# Output_Expander_IC.net
KiCad netlist of a schematic drawn in Altium Designer
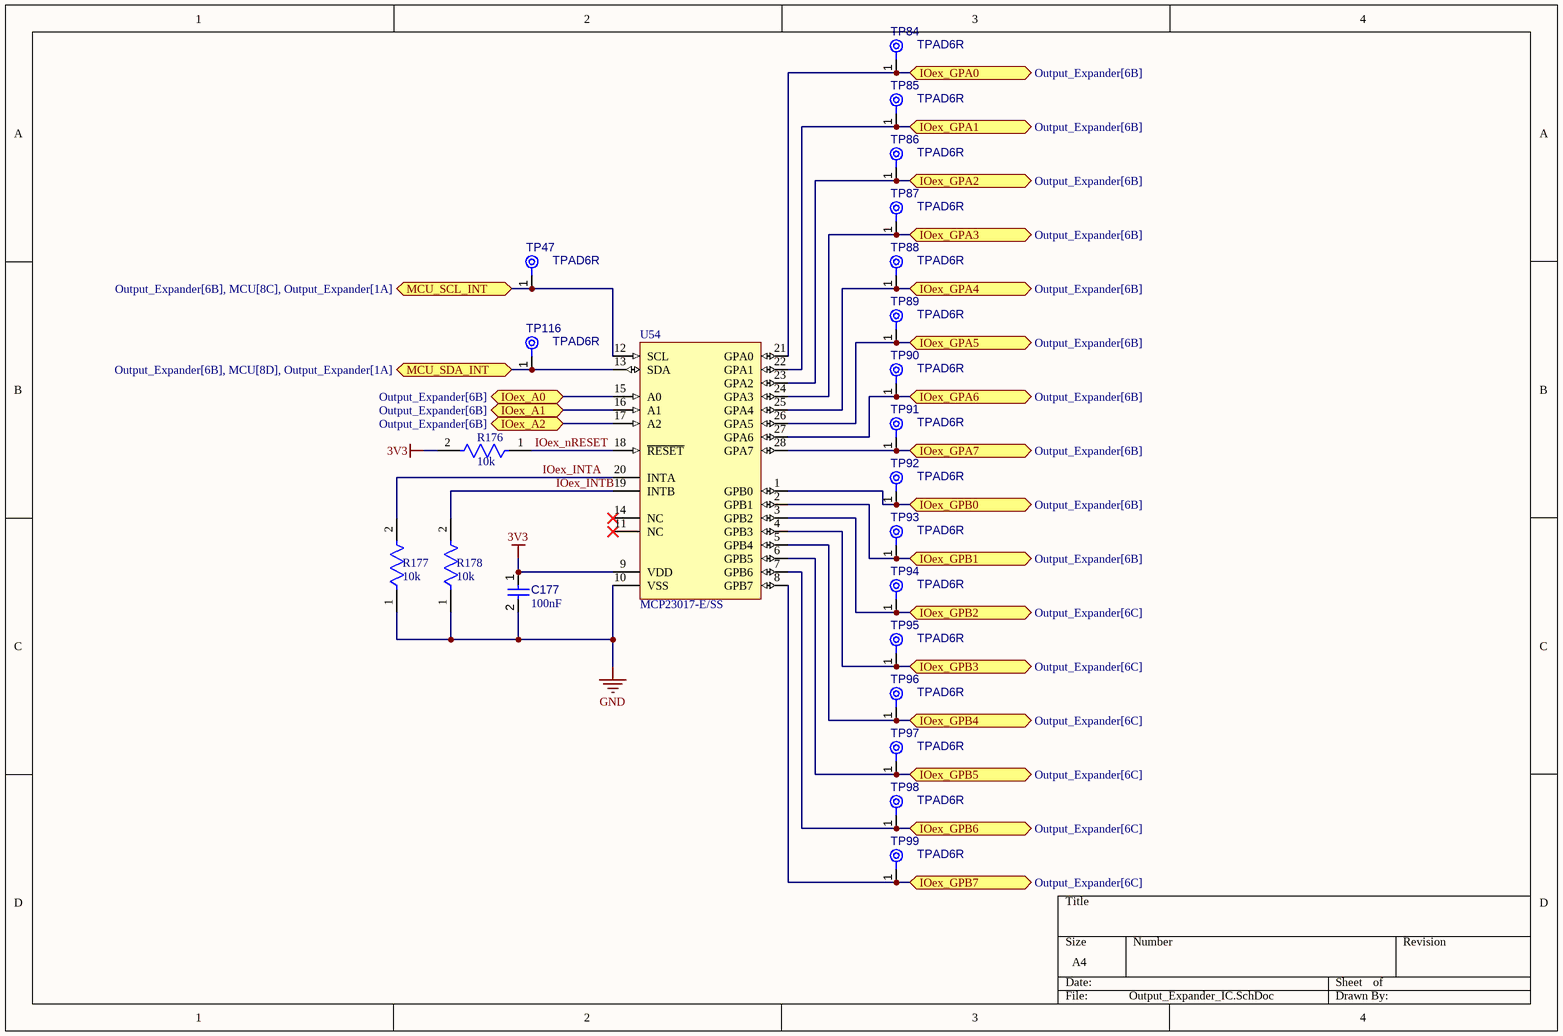
[diagram p0:  Output_Expander_IC.SchDoc]

(export (version "E")
  (design (tool "Eeschema 10.0.6"))
  (components
    (comp (ref "C177")
      (value "100nF")
      (footprint "CAPC1608X90X40NL10T20")
      (description "Chip Capacitor, 100 nF, +/- 10%, 50 V, 0603 (1608 Metric)")
      (fields (field (name "TOLERANCE") "10%") (field (name "Comment") "Capacitor 100 nF +/-10% 50 V 0603"))
      (libsource (lib "HIL RIG FYP") (part "CAP-NP-2"))
    )
    (comp (ref "R176")
      (value "10k")
      (footprint "FP-RT0603-IPC_C")
      (description "Res Thin Film 0603 10K Ohm 0.1% 1/10W ¦25ppm/¦C SMD Paper T/R")
      (fields (field (name "TOLERANCE") "0.1%") (field (name "Comment") "RT0603BRD0710KL"))
      (libsource (lib "HIL RIG FYP") (part "1029c3af85768c4190bb7ad29bc67b5"))
    )
    (comp (ref "R177")
      (value "10k")
      (footprint "FP-RT0603-IPC_C")
      (description "Res Thin Film 0603 10K Ohm 0.1% 1/10W ¦25ppm/¦C SMD Paper T/R")
      (fields (field (name "TOLERANCE") "0.1%") (field (name "Comment") "RT0603BRD0710KL"))
      (libsource (lib "HIL RIG FYP") (part "1029c3af85768c4190bb7ad29bc67b5"))
    )
    (comp (ref "R178")
      (value "10k")
      (footprint "FP-RT0603-IPC_C")
      (description "Res Thin Film 0603 10K Ohm 0.1% 1/10W ¦25ppm/¦C SMD Paper T/R")
      (fields (field (name "TOLERANCE") "0.1%") (field (name "Comment") "RT0603BRD0710KL"))
      (libsource (lib "HIL RIG FYP") (part "1029c3af85768c4190bb7ad29bc67b5"))
    )
    (comp (ref "TP47")
      (value "TPAD6R")
      (footprint "TP06R")
      (description "0.6mm round")
      (libsource (lib "HIL RIG FYP") (part "CMP-001-0001-4"))
    )
    (comp (ref "TP84")
      (value "TPAD6R")
      (footprint "TP06R")
      (description "0.6mm round")
      (libsource (lib "HIL RIG FYP") (part "CMP-001-0001-4"))
    )
    (comp (ref "TP85")
      (value "TPAD6R")
      (footprint "TP06R")
      (description "0.6mm round")
      (libsource (lib "HIL RIG FYP") (part "CMP-001-0001-4"))
    )
    (comp (ref "TP86")
      (value "TPAD6R")
      (footprint "TP06R")
      (description "0.6mm round")
      (libsource (lib "HIL RIG FYP") (part "CMP-001-0001-4"))
    )
    (comp (ref "TP87")
      (value "TPAD6R")
      (footprint "TP06R")
      (description "0.6mm round")
      (libsource (lib "HIL RIG FYP") (part "CMP-001-0001-4"))
    )
    (comp (ref "TP88")
      (value "TPAD6R")
      (footprint "TP06R")
      (description "0.6mm round")
      (libsource (lib "HIL RIG FYP") (part "CMP-001-0001-4"))
    )
    (comp (ref "TP89")
      (value "TPAD6R")
      (footprint "TP06R")
      (description "0.6mm round")
      (libsource (lib "HIL RIG FYP") (part "CMP-001-0001-4"))
    )
    (comp (ref "TP90")
      (value "TPAD6R")
      (footprint "TP06R")
      (description "0.6mm round")
      (libsource (lib "HIL RIG FYP") (part "CMP-001-0001-4"))
    )
    (comp (ref "TP91")
      (value "TPAD6R")
      (footprint "TP06R")
      (description "0.6mm round")
      (libsource (lib "HIL RIG FYP") (part "CMP-001-0001-4"))
    )
    (comp (ref "TP92")
      (value "TPAD6R")
      (footprint "TP06R")
      (description "0.6mm round")
      (libsource (lib "HIL RIG FYP") (part "CMP-001-0001-4"))
    )
    (comp (ref "TP93")
      (value "TPAD6R")
      (footprint "TP06R")
      (description "0.6mm round")
      (libsource (lib "HIL RIG FYP") (part "CMP-001-0001-4"))
    )
    (comp (ref "TP94")
      (value "TPAD6R")
      (footprint "TP06R")
      (description "0.6mm round")
      (libsource (lib "HIL RIG FYP") (part "CMP-001-0001-4"))
    )
    (comp (ref "TP95")
      (value "TPAD6R")
      (footprint "TP06R")
      (description "0.6mm round")
      (libsource (lib "HIL RIG FYP") (part "CMP-001-0001-4"))
    )
    (comp (ref "TP96")
      (value "TPAD6R")
      (footprint "TP06R")
      (description "0.6mm round")
      (libsource (lib "HIL RIG FYP") (part "CMP-001-0001-4"))
    )
    (comp (ref "TP97")
      (value "TPAD6R")
      (footprint "TP06R")
      (description "0.6mm round")
      (libsource (lib "HIL RIG FYP") (part "CMP-001-0001-4"))
    )
    (comp (ref "TP98")
      (value "TPAD6R")
      (footprint "TP06R")
      (description "0.6mm round")
      (libsource (lib "HIL RIG FYP") (part "CMP-001-0001-4"))
    )
    (comp (ref "TP99")
      (value "TPAD6R")
      (footprint "TP06R")
      (description "0.6mm round")
      (libsource (lib "HIL RIG FYP") (part "CMP-001-0001-4"))
    )
    (comp (ref "TP116")
      (value "TPAD6R")
      (footprint "TP06R")
      (description "0.6mm round")
      (libsource (lib "HIL RIG FYP") (part "CMP-001-0001-4"))
    )
    (comp (ref "U54")
      (value "MCP23017-E/SS")
      (footprint "SSOP-SS28_M")
      (description "I²C Bus IC Operating temperature: -40...+125 °C Power supply: 1.8...5.5 V Package: SSOP-20")
      (libsource (lib "HIL RIG FYP") (part "PR-BUSIC-MCP23017-28"))
    )
  )
  (nets
    (net (code "1") (name "/IOex_A0") (class "Default")
      (node (ref "U54") (pin "15") (pinfunction "A0_15") (pintype "input"))
    )
    (net (code "2") (name "/IOex_A1") (class "Default")
      (node (ref "U54") (pin "16") (pinfunction "A1_16") (pintype "input"))
    )
    (net (code "3") (name "/IOex_A2") (class "Default")
      (node (ref "U54") (pin "17") (pinfunction "A2_17") (pintype "input"))
    )
    (net (code "4") (name "/IOex_GPA0") (class "Default")
      (node (ref "TP84") (pin "1") (pinfunction "TP_1") (pintype "passive"))
      (node (ref "U54") (pin "21") (pinfunction "GPA0_21") (pintype "bidirectional"))
    )
    (net (code "5") (name "/IOex_GPA1") (class "Default")
      (node (ref "TP85") (pin "1") (pinfunction "TP_1") (pintype "passive"))
      (node (ref "U54") (pin "22") (pinfunction "GPA1_22") (pintype "bidirectional"))
    )
    (net (code "6") (name "/IOex_GPA2") (class "Default")
      (node (ref "TP86") (pin "1") (pinfunction "TP_1") (pintype "passive"))
      (node (ref "U54") (pin "23") (pinfunction "GPA2_23") (pintype "bidirectional"))
    )
    (net (code "7") (name "/IOex_GPA3") (class "Default")
      (node (ref "TP87") (pin "1") (pinfunction "TP_1") (pintype "passive"))
      (node (ref "U54") (pin "24") (pinfunction "GPA3_24") (pintype "bidirectional"))
    )
    (net (code "8") (name "/IOex_GPA4") (class "Default")
      (node (ref "TP88") (pin "1") (pinfunction "TP_1") (pintype "passive"))
      (node (ref "U54") (pin "25") (pinfunction "GPA4_25") (pintype "bidirectional"))
    )
    (net (code "9") (name "/IOex_GPA5") (class "Default")
      (node (ref "TP89") (pin "1") (pinfunction "TP_1") (pintype "passive"))
      (node (ref "U54") (pin "26") (pinfunction "GPA5_26") (pintype "bidirectional"))
    )
    (net (code "10") (name "/IOex_GPA6") (class "Default")
      (node (ref "TP90") (pin "1") (pinfunction "TP_1") (pintype "passive"))
      (node (ref "U54") (pin "27") (pinfunction "GPA6_27") (pintype "bidirectional"))
    )
    (net (code "11") (name "/IOex_GPA7") (class "Default")
      (node (ref "TP91") (pin "1") (pinfunction "TP_1") (pintype "passive"))
      (node (ref "U54") (pin "28") (pinfunction "GPA7_28") (pintype "bidirectional"))
    )
    (net (code "12") (name "/IOex_GPB0") (class "Default")
      (node (ref "TP92") (pin "1") (pinfunction "TP_1") (pintype "passive"))
      (node (ref "U54") (pin "1") (pinfunction "GPB0_1") (pintype "bidirectional"))
    )
    (net (code "13") (name "/IOex_GPB1") (class "Default")
      (node (ref "TP93") (pin "1") (pinfunction "TP_1") (pintype "passive"))
      (node (ref "U54") (pin "2") (pinfunction "GPB1_2") (pintype "bidirectional"))
    )
    (net (code "14") (name "/IOex_GPB2") (class "Default")
      (node (ref "TP94") (pin "1") (pinfunction "TP_1") (pintype "passive"))
      (node (ref "U54") (pin "3") (pinfunction "GPB2_3") (pintype "bidirectional"))
    )
    (net (code "15") (name "/IOex_GPB3") (class "Default")
      (node (ref "TP95") (pin "1") (pinfunction "TP_1") (pintype "passive"))
      (node (ref "U54") (pin "4") (pinfunction "GPB3_4") (pintype "bidirectional"))
    )
    (net (code "16") (name "/IOex_GPB4") (class "Default")
      (node (ref "TP96") (pin "1") (pinfunction "TP_1") (pintype "passive"))
      (node (ref "U54") (pin "5") (pinfunction "GPB4_5") (pintype "bidirectional"))
    )
    (net (code "17") (name "/IOex_GPB5") (class "Default")
      (node (ref "TP97") (pin "1") (pinfunction "TP_1") (pintype "passive"))
      (node (ref "U54") (pin "6") (pinfunction "GPB5_6") (pintype "bidirectional"))
    )
    (net (code "18") (name "/IOex_GPB6") (class "Default")
      (node (ref "TP98") (pin "1") (pinfunction "TP_1") (pintype "passive"))
      (node (ref "U54") (pin "7") (pinfunction "GPB6_7") (pintype "bidirectional"))
    )
    (net (code "19") (name "/IOex_GPB7") (class "Default")
      (node (ref "TP99") (pin "1") (pinfunction "TP_1") (pintype "passive"))
      (node (ref "U54") (pin "8") (pinfunction "GPB7_8") (pintype "bidirectional"))
    )
    (net (code "20") (name "/IOex_INTA") (class "Default")
      (node (ref "R177") (pin "2") (pinfunction "2_2") (pintype "passive"))
      (node (ref "U54") (pin "20") (pinfunction "INTA_20") (pintype "open_collector"))
    )
    (net (code "21") (name "/IOex_INTB") (class "Default")
      (node (ref "R178") (pin "2") (pinfunction "2_2") (pintype "passive"))
      (node (ref "U54") (pin "19") (pinfunction "INTB_19") (pintype "open_collector"))
    )
    (net (code "22") (name "/IOex_nRESET") (class "Default")
      (node (ref "R176") (pin "1") (pinfunction "1_1") (pintype "passive"))
      (node (ref "U54") (pin "18") (pinfunction "~{RESET}_18") (pintype "input"))
    )
    (net (code "23") (name "/MCU_SCL_INT") (class "Default")
      (node (ref "TP47") (pin "1") (pinfunction "TP_1") (pintype "passive"))
      (node (ref "U54") (pin "12") (pinfunction "SCL_12") (pintype "input"))
    )
    (net (code "24") (name "/MCU_SDA_INT") (class "Default")
      (node (ref "TP116") (pin "1") (pinfunction "TP_1") (pintype "passive"))
      (node (ref "U54") (pin "13") (pinfunction "SDA_13") (pintype "bidirectional"))
    )
    (net (code "25") (name "3V3") (class "Default")
      (node (ref "C177") (pin "1") (pinfunction "1_1") (pintype "passive"))
      (node (ref "R176") (pin "2") (pinfunction "2_2") (pintype "passive"))
      (node (ref "U54") (pin "9") (pinfunction "VDD_9") (pintype "power_in"))
    )
    (net (code "26") (name "GND") (class "Default")
      (node (ref "C177") (pin "2") (pinfunction "2_2") (pintype "passive"))
      (node (ref "R177") (pin "1") (pinfunction "1_1") (pintype "passive"))
      (node (ref "R178") (pin "1") (pinfunction "1_1") (pintype "passive"))
      (node (ref "U54") (pin "10") (pinfunction "VSS_10") (pintype "power_in"))
    )
    (net (code "27") (name "unconnected-(U54-NC-Pad11)") (class "Default")
      (node (ref "U54") (pin "11") (pinfunction "NC_11") (pintype "passive+no_connect"))
    )
    (net (code "28") (name "unconnected-(U54-NC-Pad14)") (class "Default")
      (node (ref "U54") (pin "14") (pinfunction "NC_14") (pintype "passive+no_connect"))
    )
  )
)
